# STM32-TX.net
KiCad netlist of a schematic drawn in EAGLE
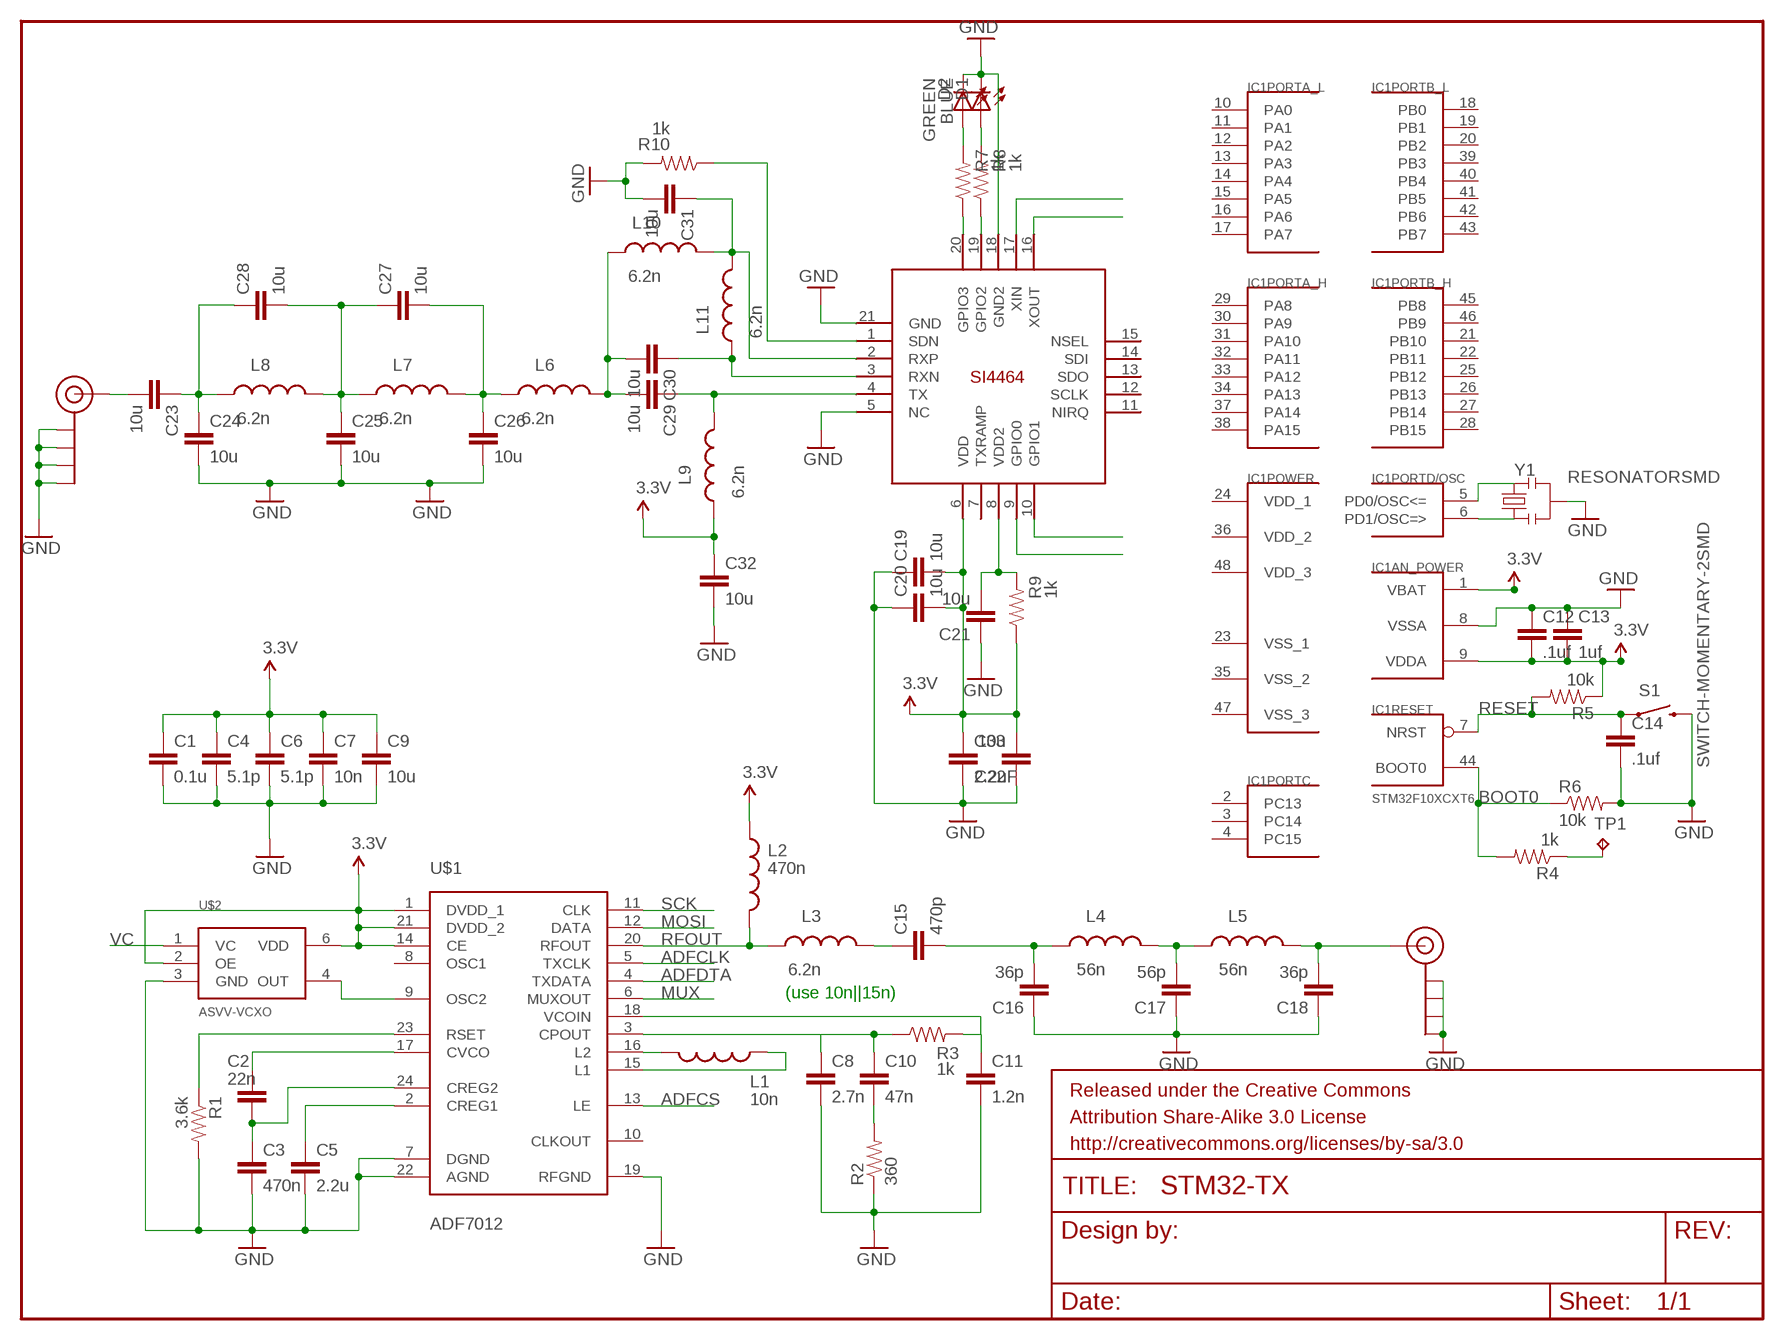
[diagram p0: schematic, sheet 1]

(export (version "E")
  (design (tool "Eeschema 10.0.6"))
  (components
    (comp (ref "C1")
      (value "0.1u")
      (footprint "eagle-import:0603-CAP")
      (libsource (lib "eagle-import") (part "SparkFun-Capacitors_CAP0603-CAP"))
    )
    (comp (ref "C2")
      (value "22n")
      (footprint "eagle-import:0603-CAP")
      (libsource (lib "eagle-import") (part "SparkFun-Capacitors_CAP0603-CAP"))
    )
    (comp (ref "C3")
      (value "470n")
      (footprint "eagle-import:0603-CAP")
      (libsource (lib "eagle-import") (part "SparkFun-Capacitors_CAP0603-CAP"))
    )
    (comp (ref "C4")
      (value "5.1p")
      (footprint "eagle-import:0603-CAP")
      (libsource (lib "eagle-import") (part "SparkFun-Capacitors_CAP0603-CAP"))
    )
    (comp (ref "C5")
      (value "2.2u")
      (footprint "eagle-import:0603-CAP")
      (libsource (lib "eagle-import") (part "SparkFun-Capacitors_CAP0603-CAP"))
    )
    (comp (ref "C6")
      (value "5.1p")
      (footprint "eagle-import:0603-CAP")
      (libsource (lib "eagle-import") (part "SparkFun-Capacitors_CAP0603-CAP"))
    )
    (comp (ref "C7")
      (value "10n")
      (footprint "eagle-import:0603-CAP")
      (libsource (lib "eagle-import") (part "SparkFun-Capacitors_CAP0603-CAP"))
    )
    (comp (ref "C8")
      (value "2.7n")
      (footprint "eagle-import:0603-CAP")
      (libsource (lib "eagle-import") (part "SparkFun-Capacitors_CAP0603-CAP"))
    )
    (comp (ref "C9")
      (value "10u")
      (footprint "eagle-import:0603-CAP")
      (libsource (lib "eagle-import") (part "SparkFun-Capacitors_CAP0603-CAP"))
    )
    (comp (ref "C10")
      (value "47n")
      (footprint "eagle-import:0603-CAP")
      (libsource (lib "eagle-import") (part "SparkFun-Capacitors_CAP0603-CAP"))
    )
    (comp (ref "C11")
      (value "1.2n")
      (footprint "eagle-import:0603-CAP")
      (libsource (lib "eagle-import") (part "SparkFun-Capacitors_CAP0603-CAP"))
    )
    (comp (ref "C12")
      (value ".1uf")
      (footprint "eagle-import:0402-CAP")
      (libsource (lib "eagle-import") (part "CAP0402-CAP"))
    )
    (comp (ref "C13")
      (value "1uf")
      (footprint "eagle-import:0402-CAP")
      (libsource (lib "eagle-import") (part "CAP0402-CAP"))
    )
    (comp (ref "C14")
      (value ".1uf")
      (footprint "eagle-import:0402-CAP")
      (libsource (lib "eagle-import") (part "CAP0402-CAP"))
    )
    (comp (ref "C15")
      (value "470p")
      (footprint "eagle-import:0603-CAP")
      (libsource (lib "eagle-import") (part "SparkFun-Capacitors_CAP0603-CAP"))
    )
    (comp (ref "C16")
      (value "36p")
      (footprint "eagle-import:0603-CAP")
      (libsource (lib "eagle-import") (part "SparkFun-Capacitors_CAP0603-CAP"))
    )
    (comp (ref "C17")
      (value "56p")
      (footprint "eagle-import:0603-CAP")
      (libsource (lib "eagle-import") (part "SparkFun-Capacitors_CAP0603-CAP"))
    )
    (comp (ref "C18")
      (value "36p")
      (footprint "eagle-import:0603-CAP")
      (libsource (lib "eagle-import") (part "SparkFun-Capacitors_CAP0603-CAP"))
    )
    (comp (ref "C19")
      (value "10u")
      (footprint "eagle-import:0603-CAP")
      (libsource (lib "eagle-import") (part "SparkFun-Capacitors_CAP0603-CAP"))
    )
    (comp (ref "C20")
      (value "10u")
      (footprint "eagle-import:0603-CAP")
      (libsource (lib "eagle-import") (part "SparkFun-Capacitors_CAP0603-CAP"))
    )
    (comp (ref "C21")
      (value "10u")
      (footprint "eagle-import:0603-CAP")
      (libsource (lib "eagle-import") (part "SparkFun-Capacitors_CAP0603-CAP"))
    )
    (comp (ref "C22")
      (value "10u")
      (footprint "eagle-import:0603-CAP")
      (libsource (lib "eagle-import") (part "SparkFun-Capacitors_CAP0603-CAP"))
    )
    (comp (ref "C23")
      (value "10u")
      (footprint "eagle-import:0603-CAP")
      (libsource (lib "eagle-import") (part "SparkFun-Capacitors_CAP0603-CAP"))
    )
    (comp (ref "C24")
      (value "10u")
      (footprint "eagle-import:0603-CAP")
      (libsource (lib "eagle-import") (part "SparkFun-Capacitors_CAP0603-CAP"))
    )
    (comp (ref "C25")
      (value "10u")
      (footprint "eagle-import:0603-CAP")
      (libsource (lib "eagle-import") (part "SparkFun-Capacitors_CAP0603-CAP"))
    )
    (comp (ref "C26")
      (value "10u")
      (footprint "eagle-import:0603-CAP")
      (libsource (lib "eagle-import") (part "SparkFun-Capacitors_CAP0603-CAP"))
    )
    (comp (ref "C27")
      (value "10u")
      (footprint "eagle-import:0603-CAP")
      (libsource (lib "eagle-import") (part "SparkFun-Capacitors_CAP0603-CAP"))
    )
    (comp (ref "C28")
      (value "10u")
      (footprint "eagle-import:0603-CAP")
      (libsource (lib "eagle-import") (part "SparkFun-Capacitors_CAP0603-CAP"))
    )
    (comp (ref "C29")
      (value "10u")
      (footprint "eagle-import:0603-CAP")
      (libsource (lib "eagle-import") (part "SparkFun-Capacitors_CAP0603-CAP"))
    )
    (comp (ref "C30")
      (value "10u")
      (footprint "eagle-import:0603-CAP")
      (libsource (lib "eagle-import") (part "SparkFun-Capacitors_CAP0603-CAP"))
    )
    (comp (ref "C31")
      (value "10u")
      (footprint "eagle-import:0603-CAP")
      (libsource (lib "eagle-import") (part "SparkFun-Capacitors_CAP0603-CAP"))
    )
    (comp (ref "C32")
      (value "10u")
      (footprint "eagle-import:0603-CAP")
      (libsource (lib "eagle-import") (part "SparkFun-Capacitors_CAP0603-CAP"))
    )
    (comp (ref "C33")
      (value "2.2uF")
      (footprint "eagle-import:1206")
      (libsource (lib "eagle-import") (part "2.2UF-CERCAP-10009"))
    )
    (comp (ref "D1")
      (value "BLUE")
      (footprint "eagle-import:LED-0603")
      (libsource (lib "eagle-import") (part "LED-BLUE0603"))
    )
    (comp (ref "D2")
      (value "GREEN")
      (footprint "eagle-import:LED-0603")
      (libsource (lib "eagle-import") (part "LED-GREEN0603"))
    )
    (comp (ref "FRAME1")
      (value "FRAME-LETTER")
      (footprint "eagle-import:CREATIVE_COMMONS")
      (libsource (lib "eagle-import") (part "FRAME-LETTER"))
    )
    (comp (ref "IC1")
      (value "STM32F10XCXT6")
      (footprint "eagle-import:TQFP48")
      (libsource (lib "eagle-import") (part "STM32F10XCXT6"))
    )
    (comp (ref "J$1")
      (value "SMA_EDGE")
      (footprint "eagle-import:SMA-EDGE")
      (libsource (lib "eagle-import") (part "SMA_EDGE"))
    )
    (comp (ref "J$2")
      (value "SMA_EDGE")
      (footprint "eagle-import:SMA-EDGE")
      (libsource (lib "eagle-import") (part "SMA_EDGE"))
    )
    (comp (ref "L1")
      (value "10n")
      (footprint "eagle-import:0603")
      (libsource (lib "eagle-import") (part "INDUCTOR0603"))
    )
    (comp (ref "L2")
      (value "470n")
      (footprint "eagle-import:0603")
      (libsource (lib "eagle-import") (part "INDUCTOR0603"))
    )
    (comp (ref "L3")
      (value "6.2n")
      (footprint "eagle-import:0603")
      (libsource (lib "eagle-import") (part "INDUCTOR0603"))
    )
    (comp (ref "L4")
      (value "56n")
      (footprint "eagle-import:C0402")
      (libsource (lib "eagle-import") (part "INDUCTOR0402"))
    )
    (comp (ref "L5")
      (value "56n")
      (footprint "eagle-import:C0402")
      (libsource (lib "eagle-import") (part "INDUCTOR0402"))
    )
    (comp (ref "L6")
      (value "6.2n")
      (footprint "eagle-import:0603")
      (libsource (lib "eagle-import") (part "INDUCTOR0603"))
    )
    (comp (ref "L7")
      (value "6.2n")
      (footprint "eagle-import:0603")
      (libsource (lib "eagle-import") (part "INDUCTOR0603"))
    )
    (comp (ref "L8")
      (value "6.2n")
      (footprint "eagle-import:0603")
      (libsource (lib "eagle-import") (part "INDUCTOR0603"))
    )
    (comp (ref "L9")
      (value "6.2n")
      (footprint "eagle-import:0603")
      (libsource (lib "eagle-import") (part "INDUCTOR0603"))
    )
    (comp (ref "L10")
      (value "6.2n")
      (footprint "eagle-import:0603")
      (libsource (lib "eagle-import") (part "INDUCTOR0603"))
    )
    (comp (ref "L11")
      (value "6.2n")
      (footprint "eagle-import:0603")
      (libsource (lib "eagle-import") (part "INDUCTOR0603"))
    )
    (comp (ref "R1")
      (value "3.6k")
      (footprint "eagle-import:0603-RES")
      (libsource (lib "eagle-import") (part "SparkFun-Passives_RESISTOR0603-RES"))
    )
    (comp (ref "R2")
      (value "360")
      (footprint "eagle-import:0603-RES")
      (libsource (lib "eagle-import") (part "SparkFun-Passives_RESISTOR0603-RES"))
    )
    (comp (ref "R3")
      (value "1k")
      (footprint "eagle-import:0603-RES")
      (libsource (lib "eagle-import") (part "SparkFun-Passives_RESISTOR0603-RES"))
    )
    (comp (ref "R4")
      (value "1k")
      (footprint "eagle-import:0402-RES")
      (libsource (lib "eagle-import") (part "RESISTOR0402-RES"))
    )
    (comp (ref "R5")
      (value "10k")
      (footprint "eagle-import:0402-RES")
      (libsource (lib "eagle-import") (part "RESISTOR0402-RES"))
    )
    (comp (ref "R6")
      (value "10k")
      (footprint "eagle-import:0402-RES")
      (libsource (lib "eagle-import") (part "RESISTOR0402-RES"))
    )
    (comp (ref "R7")
      (value "1k")
      (footprint "eagle-import:0603-RES")
      (libsource (lib "eagle-import") (part "SparkFun-Passives_RESISTOR0603-RES"))
    )
    (comp (ref "R8")
      (value "1k")
      (footprint "eagle-import:0603-RES")
      (libsource (lib "eagle-import") (part "SparkFun-Passives_RESISTOR0603-RES"))
    )
    (comp (ref "R9")
      (value "1k")
      (footprint "eagle-import:0603-RES")
      (libsource (lib "eagle-import") (part "SparkFun-Passives_RESISTOR0603-RES"))
    )
    (comp (ref "R10")
      (value "1k")
      (footprint "eagle-import:0603-RES")
      (libsource (lib "eagle-import") (part "SparkFun-Passives_RESISTOR0603-RES"))
    )
    (comp (ref "S1")
      (value "SWITCH-MOMENTARY-2SMD")
      (footprint "eagle-import:TACTILE_SWITCH_SMD")
      (libsource (lib "eagle-import") (part "SWITCH-MOMENTARY-2SMD"))
    )
    (comp (ref "TP1")
      (value "TPTP09R")
      (footprint "eagle-import:TP09R")
      (libsource (lib "eagle-import") (part "TPTP09R"))
    )
    (comp (ref "U$1")
      (value "ADF7012")
      (footprint "eagle-import:TSSOP-24")
      (libsource (lib "eagle-import") (part "ADF7012"))
    )
    (comp (ref "U$2")
      (value "ASVV-VCXO")
      (footprint "eagle-import:6-SMD")
      (libsource (lib "eagle-import") (part "ASVV-VCXO"))
    )
    (comp (ref "U$3")
      (value "SI4464")
      (footprint "eagle-import:QFN20+GNDPAD")
      (libsource (lib "eagle-import") (part "SI4464"))
    )
    (comp (ref "Y1")
      (value "RESONATORSMD")
      (footprint "eagle-import:RESONATOR-SMD")
      (libsource (lib "eagle-import") (part "RESONATORSMD"))
    )
  )
  (nets
    (net (code "1") (name "/ADFCLK") (class "Default")
      (node (ref "U$1") (pin "5") (pinfunction "TXCLK_5") (pintype "bidirectional"))
    )
    (net (code "2") (name "/ADFCS") (class "Default")
      (node (ref "U$1") (pin "13") (pinfunction "LE_13") (pintype "bidirectional"))
    )
    (net (code "3") (name "/ADFDTA") (class "Default")
      (node (ref "U$1") (pin "4") (pinfunction "TXDATA_4") (pintype "bidirectional"))
    )
    (net (code "4") (name "/BOOT0") (class "Default")
      (node (ref "IC1") (pin "44") (pinfunction "BOOT0_44") (pintype "input"))
      (node (ref "R4") (pin "2") (pinfunction "2_2") (pintype "passive"))
      (node (ref "R6") (pin "1") (pinfunction "1_1") (pintype "passive"))
    )
    (net (code "5") (name "/MOSI") (class "Default")
      (node (ref "U$1") (pin "12") (pinfunction "DATA_12") (pintype "bidirectional"))
    )
    (net (code "6") (name "/MUX") (class "Default")
      (node (ref "U$1") (pin "6") (pinfunction "MUXOUT_6") (pintype "bidirectional"))
    )
    (net (code "7") (name "/RESET") (class "Default")
      (node (ref "C14") (pin "1") (pinfunction "1_1") (pintype "passive"))
      (node (ref "IC1") (pin "7") (pinfunction "NRST_7") (pintype "input"))
      (node (ref "R5") (pin "2") (pinfunction "2_2") (pintype "passive"))
      (node (ref "S1") (pin "1") (pinfunction "1_1") (pintype "passive"))
    )
    (net (code "8") (name "/RFOUT") (class "Default")
      (node (ref "L2") (pin "2") (pinfunction "2_2") (pintype "passive"))
      (node (ref "L3") (pin "1") (pinfunction "1_1") (pintype "passive"))
      (node (ref "U$1") (pin "20") (pinfunction "RFOUT_20") (pintype "bidirectional"))
    )
    (net (code "9") (name "/SCK") (class "Default")
      (node (ref "U$1") (pin "11") (pinfunction "CLK_11") (pintype "bidirectional"))
    )
    (net (code "10") (name "/VC") (class "Default")
      (node (ref "U$2") (pin "1") (pinfunction "VC_1") (pintype "bidirectional"))
    )
    (net (code "11") (name "/VDD_1") (class "Default")
      (node (ref "IC1") (pin "24") (pinfunction "VDD_1_24") (pintype "power_in"))
    )
    (net (code "12") (name "/VDD_2") (class "Default")
      (node (ref "IC1") (pin "36") (pinfunction "VDD_2_36") (pintype "power_in"))
    )
    (net (code "13") (name "/VDD_3") (class "Default")
      (node (ref "IC1") (pin "48") (pinfunction "VDD_3_48") (pintype "power_in"))
    )
    (net (code "14") (name "/VSS_1") (class "Default")
      (node (ref "IC1") (pin "23") (pinfunction "VSS_1_23") (pintype "power_in"))
    )
    (net (code "15") (name "/VSS_2") (class "Default")
      (node (ref "IC1") (pin "35") (pinfunction "VSS_2_35") (pintype "power_in"))
    )
    (net (code "16") (name "/VSS_3") (class "Default")
      (node (ref "IC1") (pin "47") (pinfunction "VSS_3_47") (pintype "power_in"))
    )
    (net (code "17") (name "3.3V") (class "Default")
      (node (ref "C1") (pin "1") (pinfunction "1_1") (pintype "passive"))
      (node (ref "C12") (pin "2") (pinfunction "2_2") (pintype "passive"))
      (node (ref "C13") (pin "2") (pinfunction "2_2") (pintype "passive"))
      (node (ref "C19") (pin "2") (pinfunction "2_2") (pintype "passive"))
      (node (ref "C20") (pin "2") (pinfunction "2_2") (pintype "passive"))
      (node (ref "C22") (pin "2") (pinfunction "2_2") (pintype "passive"))
      (node (ref "C32") (pin "1") (pinfunction "1_1") (pintype "passive"))
      (node (ref "C33") (pin "1") (pinfunction "1_1") (pintype "passive"))
      (node (ref "C4") (pin "1") (pinfunction "1_1") (pintype "passive"))
      (node (ref "C6") (pin "1") (pinfunction "1_1") (pintype "passive"))
      (node (ref "C7") (pin "1") (pinfunction "1_1") (pintype "passive"))
      (node (ref "C9") (pin "1") (pinfunction "1_1") (pintype "passive"))
      (node (ref "IC1") (pin "1") (pinfunction "VBAT_1") (pintype "power_in"))
      (node (ref "IC1") (pin "9") (pinfunction "VDDA_9") (pintype "power_in"))
      (node (ref "L2") (pin "1") (pinfunction "1_1") (pintype "passive"))
      (node (ref "L9") (pin "1") (pinfunction "1_1") (pintype "passive"))
      (node (ref "R5") (pin "1") (pinfunction "1_1") (pintype "passive"))
      (node (ref "R9") (pin "1") (pinfunction "1_1") (pintype "passive"))
      (node (ref "U$1") (pin "1") (pinfunction "DVDD_1_1") (pintype "bidirectional"))
      (node (ref "U$1") (pin "14") (pinfunction "CE_14") (pintype "bidirectional"))
      (node (ref "U$1") (pin "21") (pinfunction "DVDD_2_21") (pintype "bidirectional"))
      (node (ref "U$2") (pin "2") (pinfunction "OE_2") (pintype "bidirectional"))
      (node (ref "U$2") (pin "6") (pinfunction "VDD_6") (pintype "bidirectional"))
      (node (ref "U$3") (pin "6") (pinfunction "VDD_6") (pintype "bidirectional"))
    )
    (net (code "18") (name "GND") (class "Default")
      (node (ref "C1") (pin "2") (pinfunction "2_2") (pintype "passive"))
      (node (ref "C11") (pin "2") (pinfunction "2_2") (pintype "passive"))
      (node (ref "C12") (pin "1") (pinfunction "1_1") (pintype "passive"))
      (node (ref "C13") (pin "1") (pinfunction "1_1") (pintype "passive"))
      (node (ref "C14") (pin "2") (pinfunction "2_2") (pintype "passive"))
      (node (ref "C16") (pin "1") (pinfunction "1_1") (pintype "passive"))
      (node (ref "C17") (pin "1") (pinfunction "1_1") (pintype "passive"))
      (node (ref "C18") (pin "1") (pinfunction "1_1") (pintype "passive"))
      (node (ref "C19") (pin "1") (pinfunction "1_1") (pintype "passive"))
      (node (ref "C20") (pin "1") (pinfunction "1_1") (pintype "passive"))
      (node (ref "C21") (pin "1") (pinfunction "1_1") (pintype "passive"))
      (node (ref "C22") (pin "1") (pinfunction "1_1") (pintype "passive"))
      (node (ref "C24") (pin "2") (pinfunction "2_2") (pintype "passive"))
      (node (ref "C25") (pin "2") (pinfunction "2_2") (pintype "passive"))
      (node (ref "C26") (pin "2") (pinfunction "2_2") (pintype "passive"))
      (node (ref "C3") (pin "2") (pinfunction "2_2") (pintype "passive"))
      (node (ref "C31") (pin "2") (pinfunction "2_2") (pintype "passive"))
      (node (ref "C32") (pin "2") (pinfunction "2_2") (pintype "passive"))
      (node (ref "C33") (pin "2") (pinfunction "2_2") (pintype "passive"))
      (node (ref "C4") (pin "2") (pinfunction "2_2") (pintype "passive"))
      (node (ref "C5") (pin "2") (pinfunction "2_2") (pintype "passive"))
      (node (ref "C6") (pin "2") (pinfunction "2_2") (pintype "passive"))
      (node (ref "C7") (pin "2") (pinfunction "2_2") (pintype "passive"))
      (node (ref "C8") (pin "2") (pinfunction "2_2") (pintype "passive"))
      (node (ref "C9") (pin "2") (pinfunction "2_2") (pintype "passive"))
      (node (ref "D1") (pin "C") (pinfunction "C_C") (pintype "passive"))
      (node (ref "D2") (pin "C") (pinfunction "C_C") (pintype "passive"))
      (node (ref "IC1") (pin "8") (pinfunction "VSSA_8") (pintype "power_in"))
      (node (ref "J$1") (pin "GND@0") (pinfunction "GND_GND@0") (pintype "bidirectional"))
      (node (ref "J$1") (pin "GND@1") (pinfunction "GND_GND@1") (pintype "bidirectional"))
      (node (ref "J$1") (pin "GND@2") (pinfunction "GND_GND@2") (pintype "bidirectional"))
      (node (ref "J$1") (pin "GND@3") (pinfunction "GND_GND@3") (pintype "bidirectional"))
      (node (ref "J$2") (pin "GND@0") (pinfunction "GND_GND@0") (pintype "bidirectional"))
      (node (ref "J$2") (pin "GND@1") (pinfunction "GND_GND@1") (pintype "bidirectional"))
      (node (ref "J$2") (pin "GND@2") (pinfunction "GND_GND@2") (pintype "bidirectional"))
      (node (ref "J$2") (pin "GND@3") (pinfunction "GND_GND@3") (pintype "bidirectional"))
      (node (ref "R1") (pin "2") (pinfunction "2_2") (pintype "passive"))
      (node (ref "R10") (pin "2") (pinfunction "2_2") (pintype "passive"))
      (node (ref "R2") (pin "1") (pinfunction "1_1") (pintype "passive"))
      (node (ref "R6") (pin "2") (pinfunction "2_2") (pintype "passive"))
      (node (ref "S1") (pin "3") (pinfunction "2_3") (pintype "passive"))
      (node (ref "U$1") (pin "19") (pinfunction "RFGND_19") (pintype "bidirectional"))
      (node (ref "U$1") (pin "22") (pinfunction "AGND_22") (pintype "bidirectional"))
      (node (ref "U$1") (pin "7") (pinfunction "DGND_7") (pintype "bidirectional"))
      (node (ref "U$2") (pin "3") (pinfunction "GND_3") (pintype "bidirectional"))
      (node (ref "U$3") (pin "18") (pinfunction "GND2_18") (pintype "bidirectional"))
      (node (ref "U$3") (pin "21") (pinfunction "GND_21") (pintype "bidirectional"))
      (node (ref "U$3") (pin "5") (pinfunction "NC _5") (pintype "bidirectional"))
      (node (ref "Y1") (pin "2") (pinfunction "2_2") (pintype "passive"))
    )
    (net (code "19") (name "Net-(C10-Pad2)") (class "Default")
      (node (ref "C10") (pin "2") (pinfunction "2_2") (pintype "passive"))
      (node (ref "R2") (pin "2") (pinfunction "2_2") (pintype "passive"))
    )
    (net (code "20") (name "Net-(C15-Pad1)") (class "Default")
      (node (ref "C15") (pin "1") (pinfunction "1_1") (pintype "passive"))
      (node (ref "L3") (pin "2") (pinfunction "2_2") (pintype "passive"))
    )
    (net (code "21") (name "Net-(C15-Pad2)") (class "Default")
      (node (ref "C15") (pin "2") (pinfunction "2_2") (pintype "passive"))
      (node (ref "C16") (pin "2") (pinfunction "2_2") (pintype "passive"))
      (node (ref "L4") (pin "1") (pinfunction "1_1") (pintype "passive"))
    )
    (net (code "22") (name "Net-(C17-Pad2)") (class "Default")
      (node (ref "C17") (pin "2") (pinfunction "2_2") (pintype "passive"))
      (node (ref "L4") (pin "2") (pinfunction "2_2") (pintype "passive"))
      (node (ref "L5") (pin "1") (pinfunction "1_1") (pintype "passive"))
    )
    (net (code "23") (name "Net-(C23-Pad1)") (class "Default")
      (node (ref "C23") (pin "1") (pinfunction "1_1") (pintype "passive"))
      (node (ref "C24") (pin "1") (pinfunction "1_1") (pintype "passive"))
      (node (ref "C28") (pin "1") (pinfunction "1_1") (pintype "passive"))
      (node (ref "L8") (pin "1") (pinfunction "1_1") (pintype "passive"))
    )
    (net (code "24") (name "Net-(C25-Pad1)") (class "Default")
      (node (ref "C25") (pin "1") (pinfunction "1_1") (pintype "passive"))
      (node (ref "C27") (pin "1") (pinfunction "1_1") (pintype "passive"))
      (node (ref "C28") (pin "2") (pinfunction "2_2") (pintype "passive"))
      (node (ref "L7") (pin "1") (pinfunction "1_1") (pintype "passive"))
      (node (ref "L8") (pin "2") (pinfunction "2_2") (pintype "passive"))
    )
    (net (code "25") (name "Net-(C26-Pad1)") (class "Default")
      (node (ref "C26") (pin "1") (pinfunction "1_1") (pintype "passive"))
      (node (ref "C27") (pin "2") (pinfunction "2_2") (pintype "passive"))
      (node (ref "L6") (pin "1") (pinfunction "1_1") (pintype "passive"))
      (node (ref "L7") (pin "2") (pinfunction "2_2") (pintype "passive"))
    )
    (net (code "26") (name "Net-(C29-Pad2)") (class "Default")
      (node (ref "C29") (pin "2") (pinfunction "2_2") (pintype "passive"))
      (node (ref "C30") (pin "2") (pinfunction "2_2") (pintype "passive"))
      (node (ref "L10") (pin "1") (pinfunction "1_1") (pintype "passive"))
      (node (ref "L6") (pin "2") (pinfunction "2_2") (pintype "passive"))
    )
    (net (code "27") (name "Net-(D1-PadA)") (class "Default")
      (node (ref "D1") (pin "A") (pinfunction "A_A") (pintype "passive"))
      (node (ref "R8") (pin "2") (pinfunction "2_2") (pintype "passive"))
    )
    (net (code "28") (name "Net-(D2-PadA)") (class "Default")
      (node (ref "D2") (pin "A") (pinfunction "A_A") (pintype "passive"))
      (node (ref "R7") (pin "2") (pinfunction "2_2") (pintype "passive"))
    )
    (net (code "29") (name "Net-(IC1G-PD0{slash}OSC<=)") (class "Default")
      (node (ref "IC1") (pin "5") (pinfunction "PD0/OSC<=_5") (pintype "bidirectional"))
      (node (ref "Y1") (pin "3") (pinfunction "3_3") (pintype "passive"))
    )
    (net (code "30") (name "Net-(IC1G-PD1{slash}OSC=>)") (class "Default")
      (node (ref "IC1") (pin "6") (pinfunction "PD1/OSC=>_6") (pintype "bidirectional"))
      (node (ref "Y1") (pin "1") (pinfunction "1_1") (pintype "passive"))
    )
    (net (code "31") (name "Net-(J$1-SIGNAL)") (class "Default")
      (node (ref "C18") (pin "2") (pinfunction "2_2") (pintype "passive"))
      (node (ref "J$1") (pin "SIG") (pinfunction "SIGNAL_SIG") (pintype "bidirectional"))
      (node (ref "L5") (pin "2") (pinfunction "2_2") (pintype "passive"))
    )
    (net (code "32") (name "Net-(J$2-SIGNAL)") (class "Default")
      (node (ref "C23") (pin "2") (pinfunction "2_2") (pintype "passive"))
      (node (ref "J$2") (pin "SIG") (pinfunction "SIGNAL_SIG") (pintype "bidirectional"))
    )
    (net (code "33") (name "Net-(R4-Pad1)") (class "Default")
      (node (ref "R4") (pin "1") (pinfunction "1_1") (pintype "passive"))
      (node (ref "TP1") (pin "TP") (pinfunction "TP_TP") (pintype "input"))
    )
    (net (code "34") (name "Net-(U$1-CPOUT)") (class "Default")
      (node (ref "C10") (pin "1") (pinfunction "1_1") (pintype "passive"))
      (node (ref "C8") (pin "1") (pinfunction "1_1") (pintype "passive"))
      (node (ref "R3") (pin "1") (pinfunction "1_1") (pintype "passive"))
      (node (ref "U$1") (pin "3") (pinfunction "CPOUT_3") (pintype "bidirectional"))
    )
    (net (code "35") (name "Net-(U$1-CREG1)") (class "Default")
      (node (ref "C5") (pin "1") (pinfunction "1_1") (pintype "passive"))
      (node (ref "U$1") (pin "2") (pinfunction "CREG1_2") (pintype "bidirectional"))
    )
    (net (code "36") (name "Net-(U$1-CREG2)") (class "Default")
      (node (ref "C2") (pin "2") (pinfunction "2_2") (pintype "passive"))
      (node (ref "C3") (pin "1") (pinfunction "1_1") (pintype "passive"))
      (node (ref "U$1") (pin "24") (pinfunction "CREG2_24") (pintype "bidirectional"))
    )
    (net (code "37") (name "Net-(U$1-CVCO)") (class "Default")
      (node (ref "C2") (pin "1") (pinfunction "1_1") (pintype "passive"))
      (node (ref "U$1") (pin "17") (pinfunction "CVCO_17") (pintype "bidirectional"))
    )
    (net (code "38") (name "Net-(U$1-L1)") (class "Default")
      (node (ref "L1") (pin "1") (pinfunction "1_1") (pintype "passive"))
      (node (ref "U$1") (pin "15") (pinfunction "L1_15") (pintype "bidirectional"))
    )
    (net (code "39") (name "Net-(U$1-L2)") (class "Default")
      (node (ref "L1") (pin "2") (pinfunction "2_2") (pintype "passive"))
      (node (ref "U$1") (pin "16") (pinfunction "L2_16") (pintype "bidirectional"))
    )
    (net (code "40") (name "Net-(U$1-OSC2)") (class "Default")
      (node (ref "U$1") (pin "9") (pinfunction "OSC2_9") (pintype "bidirectional"))
      (node (ref "U$2") (pin "4") (pinfunction "OUT_4") (pintype "bidirectional"))
    )
    (net (code "41") (name "Net-(U$1-RSET)") (class "Default")
      (node (ref "R1") (pin "1") (pinfunction "1_1") (pintype "passive"))
      (node (ref "U$1") (pin "23") (pinfunction "RSET_23") (pintype "bidirectional"))
    )
    (net (code "42") (name "Net-(U$1-VCOIN)") (class "Default")
      (node (ref "C11") (pin "1") (pinfunction "1_1") (pintype "passive"))
      (node (ref "R3") (pin "2") (pinfunction "2_2") (pintype "passive"))
      (node (ref "U$1") (pin "18") (pinfunction "VCOIN_18") (pintype "bidirectional"))
    )
    (net (code "43") (name "Net-(U$3-GPIO2)") (class "Default")
      (node (ref "R8") (pin "1") (pinfunction "1_1") (pintype "passive"))
      (node (ref "U$3") (pin "19") (pinfunction "GPIO2_19") (pintype "bidirectional"))
    )
    (net (code "44") (name "Net-(U$3-GPIO3)") (class "Default")
      (node (ref "R7") (pin "1") (pinfunction "1_1") (pintype "passive"))
      (node (ref "U$3") (pin "20") (pinfunction "GPIO3_20") (pintype "bidirectional"))
    )
    (net (code "45") (name "Net-(U$3-RXN)") (class "Default")
      (node (ref "C30") (pin "1") (pinfunction "1_1") (pintype "passive"))
      (node (ref "L11") (pin "1") (pinfunction "1_1") (pintype "passive"))
      (node (ref "U$3") (pin "3") (pinfunction "RXN_3") (pintype "bidirectional"))
    )
    (net (code "46") (name "Net-(U$3-RXP)") (class "Default")
      (node (ref "C31") (pin "1") (pinfunction "1_1") (pintype "passive"))
      (node (ref "L10") (pin "2") (pinfunction "2_2") (pintype "passive"))
      (node (ref "L11") (pin "2") (pinfunction "2_2") (pintype "passive"))
      (node (ref "U$3") (pin "2") (pinfunction "RXP_2") (pintype "bidirectional"))
    )
    (net (code "47") (name "Net-(U$3-SDN)") (class "Default")
      (node (ref "R10") (pin "1") (pinfunction "1_1") (pintype "passive"))
      (node (ref "U$3") (pin "1") (pinfunction "SDN_1") (pintype "bidirectional"))
    )
    (net (code "48") (name "Net-(U$3-TX)") (class "Default")
      (node (ref "C29") (pin "1") (pinfunction "1_1") (pintype "passive"))
      (node (ref "L9") (pin "2") (pinfunction "2_2") (pintype "passive"))
      (node (ref "U$3") (pin "4") (pinfunction "TX_4") (pintype "bidirectional"))
    )
    (net (code "49") (name "Net-(U$3-VDD2)") (class "Default")
      (node (ref "C21") (pin "2") (pinfunction "2_2") (pintype "passive"))
      (node (ref "R9") (pin "2") (pinfunction "2_2") (pintype "passive"))
      (node (ref "U$3") (pin "8") (pinfunction "VDD2_8") (pintype "bidirectional"))
    )
    (net (code "50") (name "unconnected-(IC1B-PA8-Pad29)") (class "Default")
      (node (ref "IC1") (pin "29") (pinfunction "PA8_29") (pintype "bidirectional"))
    )
    (net (code "51") (name "unconnected-(IC1B-PA9-Pad30)") (class "Default")
      (node (ref "IC1") (pin "30") (pinfunction "PA9_30") (pintype "bidirectional"))
    )
    (net (code "52") (name "unconnected-(IC1B-PA10-Pad31)") (class "Default")
      (node (ref "IC1") (pin "31") (pinfunction "PA10_31") (pintype "bidirectional"))
    )
    (net (code "53") (name "unconnected-(IC1B-PA11-Pad32)") (class "Default")
      (node (ref "IC1") (pin "32") (pinfunction "PA11_32") (pintype "bidirectional"))
    )
    (net (code "54") (name "unconnected-(IC1B-PA12-Pad33)") (class "Default")
      (node (ref "IC1") (pin "33") (pinfunction "PA12_33") (pintype "bidirectional"))
    )
    (net (code "55") (name "unconnected-(IC1B-PA13-Pad34)") (class "Default")
      (node (ref "IC1") (pin "34") (pinfunction "PA13_34") (pintype "bidirectional"))
    )
    (net (code "56") (name "unconnected-(IC1B-PA14-Pad37)") (class "Default")
      (node (ref "IC1") (pin "37") (pinfunction "PA14_37") (pintype "bidirectional"))
    )
    (net (code "57") (name "unconnected-(IC1B-PA15-Pad38)") (class "Default")
      (node (ref "IC1") (pin "38") (pinfunction "PA15_38") (pintype "bidirectional"))
    )
    (net (code "58") (name "unconnected-(IC1C-PA0-Pad10)") (class "Default")
      (node (ref "IC1") (pin "10") (pinfunction "PA0_10") (pintype "bidirectional"))
    )
    (net (code "59") (name "unconnected-(IC1C-PA1-Pad11)") (class "Default")
      (node (ref "IC1") (pin "11") (pinfunction "PA1_11") (pintype "bidirectional"))
    )
    (net (code "60") (name "unconnected-(IC1C-PA2-Pad12)") (class "Default")
      (node (ref "IC1") (pin "12") (pinfunction "PA2_12") (pintype "bidirectional"))
    )
    (net (code "61") (name "unconnected-(IC1C-PA3-Pad13)") (class "Default")
      (node (ref "IC1") (pin "13") (pinfunction "PA3_13") (pintype "bidirectional"))
    )
    (net (code "62") (name "unconnected-(IC1C-PA4-Pad14)") (class "Default")
      (node (ref "IC1") (pin "14") (pinfunction "PA4_14") (pintype "bidirectional"))
    )
    (net (code "63") (name "unconnected-(IC1C-PA5-Pad15)") (class "Default")
      (node (ref "IC1") (pin "15") (pinfunction "PA5_15") (pintype "bidirectional"))
    )
    (net (code "64") (name "unconnected-(IC1C-PA6-Pad16)") (class "Default")
      (node (ref "IC1") (pin "16") (pinfunction "PA6_16") (pintype "bidirectional"))
    )
    (net (code "65") (name "unconnected-(IC1C-PA7-Pad17)") (class "Default")
      (node (ref "IC1") (pin "17") (pinfunction "PA7_17") (pintype "bidirectional"))
    )
    (net (code "66") (name "unconnected-(IC1D-PB8-Pad45)") (class "Default")
      (node (ref "IC1") (pin "45") (pinfunction "PB8_45") (pintype "bidirectional"))
    )
    (net (code "67") (name "unconnected-(IC1D-PB9-Pad46)") (class "Default")
      (node (ref "IC1") (pin "46") (pinfunction "PB9_46") (pintype "bidirectional"))
    )
    (net (code "68") (name "unconnected-(IC1D-PB10-Pad21)") (class "Default")
      (node (ref "IC1") (pin "21") (pinfunction "PB10_21") (pintype "bidirectional"))
    )
    (net (code "69") (name "unconnected-(IC1D-PB11-Pad22)") (class "Default")
      (node (ref "IC1") (pin "22") (pinfunction "PB11_22") (pintype "bidirectional"))
    )
    (net (code "70") (name "unconnected-(IC1D-PB12-Pad25)") (class "Default")
      (node (ref "IC1") (pin "25") (pinfunction "PB12_25") (pintype "bidirectional"))
    )
    (net (code "71") (name "unconnected-(IC1D-PB13-Pad26)") (class "Default")
      (node (ref "IC1") (pin "26") (pinfunction "PB13_26") (pintype "bidirectional"))
    )
    (net (code "72") (name "unconnected-(IC1D-PB14-Pad27)") (class "Default")
      (node (ref "IC1") (pin "27") (pinfunction "PB14_27") (pintype "bidirectional"))
    )
    (net (code "73") (name "unconnected-(IC1D-PB15-Pad28)") (class "Default")
      (node (ref "IC1") (pin "28") (pinfunction "PB15_28") (pintype "bidirectional"))
    )
    (net (code "74") (name "unconnected-(IC1E-PB0-Pad18)") (class "Default")
      (node (ref "IC1") (pin "18") (pinfunction "PB0_18") (pintype "bidirectional"))
    )
    (net (code "75") (name "unconnected-(IC1E-PB1-Pad19)") (class "Default")
      (node (ref "IC1") (pin "19") (pinfunction "PB1_19") (pintype "bidirectional"))
    )
    (net (code "76") (name "unconnected-(IC1E-PB2-Pad20)") (class "Default")
      (node (ref "IC1") (pin "20") (pinfunction "PB2_20") (pintype "bidirectional"))
    )
    (net (code "77") (name "unconnected-(IC1E-PB3-Pad39)") (class "Default")
      (node (ref "IC1") (pin "39") (pinfunction "PB3_39") (pintype "bidirectional"))
    )
    (net (code "78") (name "unconnected-(IC1E-PB4-Pad40)") (class "Default")
      (node (ref "IC1") (pin "40") (pinfunction "PB4_40") (pintype "bidirectional"))
    )
    (net (code "79") (name "unconnected-(IC1E-PB5-Pad41)") (class "Default")
      (node (ref "IC1") (pin "41") (pinfunction "PB5_41") (pintype "bidirectional"))
    )
    (net (code "80") (name "unconnected-(IC1E-PB6-Pad42)") (class "Default")
      (node (ref "IC1") (pin "42") (pinfunction "PB6_42") (pintype "bidirectional"))
    )
    (net (code "81") (name "unconnected-(IC1E-PB7-Pad43)") (class "Default")
      (node (ref "IC1") (pin "43") (pinfunction "PB7_43") (pintype "bidirectional"))
    )
    (net (code "82") (name "unconnected-(IC1F-PC13-Pad2)") (class "Default")
      (node (ref "IC1") (pin "2") (pinfunction "PC13_2") (pintype "bidirectional"))
    )
    (net (code "83") (name "unconnected-(IC1F-PC14-Pad3)") (class "Default")
      (node (ref "IC1") (pin "3") (pinfunction "PC14_3") (pintype "bidirectional"))
    )
    (net (code "84") (name "unconnected-(IC1F-PC15-Pad4)") (class "Default")
      (node (ref "IC1") (pin "4") (pinfunction "PC15_4") (pintype "bidirectional"))
    )
    (net (code "85") (name "unconnected-(U$1-CLKOUT-Pad10)") (class "Default")
      (node (ref "U$1") (pin "10") (pinfunction "CLKOUT_10") (pintype "bidirectional"))
    )
    (net (code "86") (name "unconnected-(U$1-OSC1-Pad8)") (class "Default")
      (node (ref "U$1") (pin "8") (pinfunction "OSC1_8") (pintype "bidirectional"))
    )
    (net (code "87") (name "unconnected-(U$3-GPIO0-Pad9)") (class "Default")
      (node (ref "U$3") (pin "9") (pinfunction "GPIO0_9") (pintype "bidirectional"))
    )
    (net (code "88") (name "unconnected-(U$3-GPIO1-Pad10)") (class "Default")
      (node (ref "U$3") (pin "10") (pinfunction "GPIO1_10") (pintype "bidirectional"))
    )
    (net (code "89") (name "unconnected-(U$3-NIRQ-Pad11)") (class "Default")
      (node (ref "U$3") (pin "11") (pinfunction "NIRQ_11") (pintype "bidirectional"))
    )
    (net (code "90") (name "unconnected-(U$3-NSEL-Pad15)") (class "Default")
      (node (ref "U$3") (pin "15") (pinfunction "NSEL_15") (pintype "bidirectional"))
    )
    (net (code "91") (name "unconnected-(U$3-SCLK-Pad12)") (class "Default")
      (node (ref "U$3") (pin "12") (pinfunction "SCLK_12") (pintype "bidirectional"))
    )
    (net (code "92") (name "unconnected-(U$3-SDI-Pad14)") (class "Default")
      (node (ref "U$3") (pin "14") (pinfunction "SDI_14") (pintype "bidirectional"))
    )
    (net (code "93") (name "unconnected-(U$3-SDO-Pad13)") (class "Default")
      (node (ref "U$3") (pin "13") (pinfunction "SDO_13") (pintype "bidirectional"))
    )
    (net (code "94") (name "unconnected-(U$3-TXRAMP-Pad7)") (class "Default")
      (node (ref "U$3") (pin "7") (pinfunction "TXRAMP_7") (pintype "bidirectional"))
    )
    (net (code "95") (name "unconnected-(U$3-XIN-Pad17)") (class "Default")
      (node (ref "U$3") (pin "17") (pinfunction "XIN_17") (pintype "bidirectional"))
    )
    (net (code "96") (name "unconnected-(U$3-XOUT-Pad16)") (class "Default")
      (node (ref "U$3") (pin "16") (pinfunction "XOUT_16") (pintype "bidirectional"))
    )
  )
)
